# PSU_1084_ADJ.net
KiCad netlist of a schematic drawn in Altium Designer
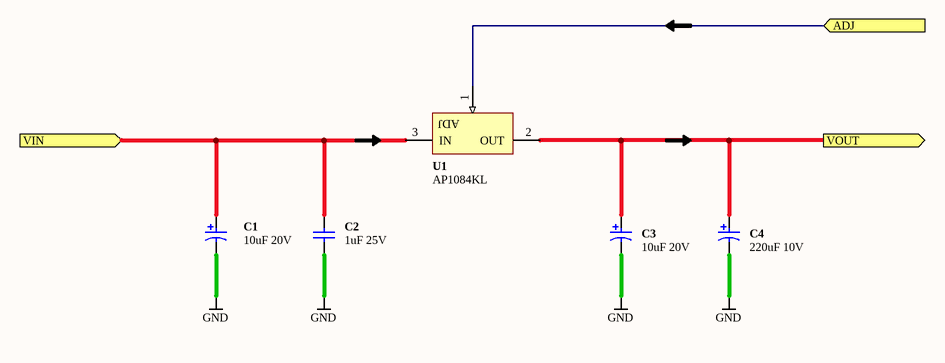
[diagram p0: PSU_1084_ADJ.SchDoc]

(export (version "E")
  (design (tool "Eeschema 10.0.6"))
  (components
    (comp (ref "C1")
      (value "10uF 20V")
      (footprint "CAPC3528-STAR")
      (description "Capacitor, Tantalum, 10uF 10% 20V MCCT-B (3528)")
      (fields (field (name "TOLERANCE") "10 %"))
      (libsource (lib "altium-import") (part "root_0_CAP-P_"))
    )
    (comp (ref "C2")
      (value "1uF 25V")
      (footprint "CAPC3216-STAR")
      (description "Capacitor, Ceramic, 1uF 10% 25V 1206 (3216) X7R")
      (fields (field (name "TOLERANCE") "10 %"))
      (libsource (lib "altium-import") (part "root_0_CAP-NP_"))
    )
    (comp (ref "C3")
      (value "10uF 20V")
      (footprint "CAPC3528-STAR")
      (description "Capacitor, Tantalum, 10uF 10% 20V MCCT-B (3528)")
      (fields (field (name "TOLERANCE") "10 %"))
      (libsource (lib "altium-import") (part "root_0_CAP-P_"))
    )
    (comp (ref "C4")
      (value "220uF 10V")
      (footprint "CAPC7343-STAR")
      (description "Capacitor, Tantalum, 220uF 10% 10V MCCT-D (7343-31)")
      (fields (field (name "TOLERANCE") "10 %"))
      (libsource (lib "altium-import") (part "root_0_CAP-P_"))
    )
    (comp (ref "U1")
      (value "AP1084KL")
      (footprint "TO254P-3N")
      (description "AP1084KL, 5A Low Dropout Positive Adjustable Regulator")
      (libsource (lib "AltiumDesignLibrary") (part "AP1084KL"))
    )
  )
  (nets
    (net (code "1") (name "/ADJ") (class "Default")
      (node (ref "U1") (pin "1") (pinfunction "ADJ_1") (pintype "input"))
    )
    (net (code "2") (name "/VIN") (class "Default")
      (node (ref "C1") (pin "1") (pinfunction "1_1") (pintype "passive"))
      (node (ref "C2") (pin "1") (pinfunction "1_1") (pintype "passive"))
      (node (ref "U1") (pin "3") (pinfunction "IN_3") (pintype "power_in"))
    )
    (net (code "3") (name "/VOUT") (class "Default")
      (node (ref "C3") (pin "1") (pinfunction "1_1") (pintype "passive"))
      (node (ref "C4") (pin "1") (pinfunction "1_1") (pintype "passive"))
      (node (ref "U1") (pin "2") (pinfunction "OUT_2") (pintype "power_in"))
    )
    (net (code "4") (name "GND") (class "Default")
      (node (ref "C1") (pin "2") (pinfunction "2_2") (pintype "passive"))
      (node (ref "C2") (pin "2") (pinfunction "2_2") (pintype "passive"))
      (node (ref "C3") (pin "2") (pinfunction "2_2") (pintype "passive"))
      (node (ref "C4") (pin "2") (pinfunction "2_2") (pintype "passive"))
    )
  )
)
